# Sheet1.net
KiCad netlist of a schematic drawn in Altium Designer
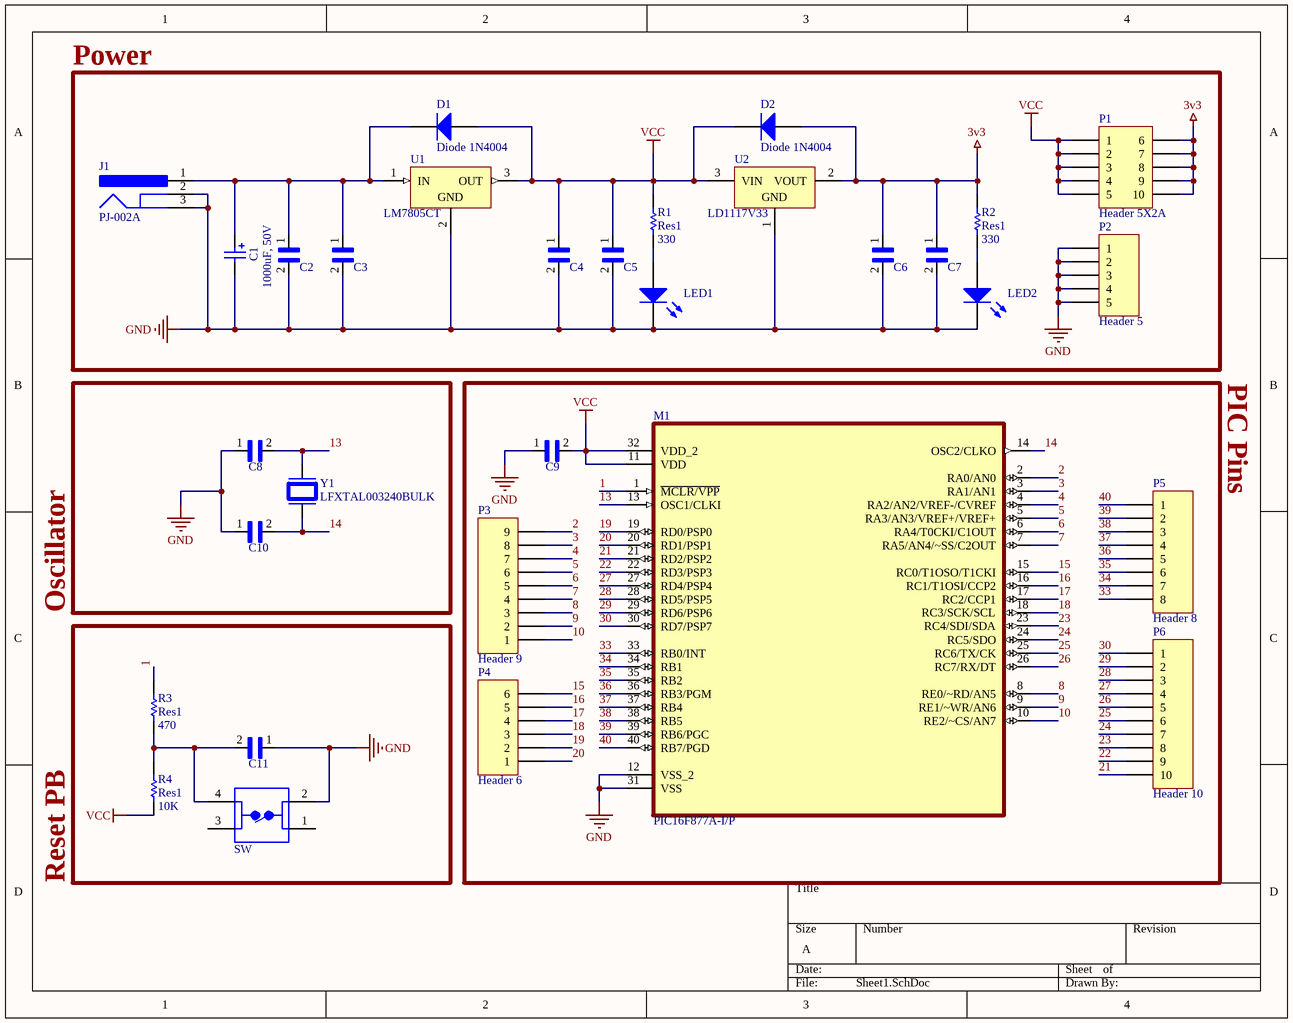
[diagram p0: Sheet1.SchDoc]

(export (version "E")
  (design (tool "Eeschema 10.0.6"))
  (components
    (comp (ref "C1")
      (value "1000uF, 50V")
      (footprint "WCAP-ATG8_D13H25")
      (description "WCAP-ATG8 Aluminum Electrolytic Capacitor, Radial, THT, D13xH25, 1000uF, 50V")
      (fields
        (field (name "MANUFACTURER PART NUMBER") "860010678024")
        (field (name "MANUFACTURER") "Wurth Elektronik")
      )
      (libsource (lib "Aluminium Electrolyt Capacitors") (part "860010678024"))
    )
    (comp (ref "C2")
      (value "RDE5C2A220J0M1H03A")
      (footprint "CAP_RDE5C2A220J0M1H03A")
      (description "Lead Capacitor C0G_EIA_ with Capacitance: 22pF and Rated Voltage: 100Vdc")
      (fields (field (name "MF") "Murata"))
      (libsource (lib "Schlib1") (part "RDE5C2A220J0M1H03A"))
    )
    (comp (ref "C3")
      (value "RDE5C2A220J0M1H03A")
      (footprint "CAP_RDE5C2A220J0M1H03A")
      (description "Lead Capacitor C0G_EIA_ with Capacitance: 22pF and Rated Voltage: 100Vdc")
      (fields (field (name "MF") "Murata"))
      (libsource (lib "Schlib1") (part "RDE5C2A220J0M1H03A"))
    )
    (comp (ref "C4")
      (value "RDE5C2A220J0M1H03A")
      (footprint "CAP_RDE5C2A220J0M1H03A")
      (description "Lead Capacitor C0G_EIA_ with Capacitance: 22pF and Rated Voltage: 100Vdc")
      (fields (field (name "MF") "Murata"))
      (libsource (lib "Schlib1") (part "RDE5C2A220J0M1H03A"))
    )
    (comp (ref "C5")
      (value "RDE5C2A220J0M1H03A")
      (footprint "CAP_RDE5C2A220J0M1H03A")
      (description "Lead Capacitor C0G_EIA_ with Capacitance: 22pF and Rated Voltage: 100Vdc")
      (fields (field (name "MF") "Murata"))
      (libsource (lib "Schlib1") (part "RDE5C2A220J0M1H03A"))
    )
    (comp (ref "C6")
      (value "RDE5C2A220J0M1H03A")
      (footprint "CAP_RDE5C2A220J0M1H03A")
      (description "Lead Capacitor C0G_EIA_ with Capacitance: 22pF and Rated Voltage: 100Vdc")
      (fields (field (name "MF") "Murata"))
      (libsource (lib "Schlib1") (part "RDE5C2A220J0M1H03A"))
    )
    (comp (ref "C7")
      (value "RDE5C2A220J0M1H03A")
      (footprint "CAP_RDE5C2A220J0M1H03A")
      (description "Lead Capacitor C0G_EIA_ with Capacitance: 22pF and Rated Voltage: 100Vdc")
      (fields (field (name "MF") "Murata"))
      (libsource (lib "Schlib1") (part "RDE5C2A220J0M1H03A"))
    )
    (comp (ref "C8")
      (value "RDE5C2A220J0M1H03A")
      (footprint "CAP_RDE5C2A220J0M1H03A")
      (description "Lead Capacitor C0G_EIA_ with Capacitance: 22pF and Rated Voltage: 100Vdc")
      (fields (field (name "MF") "Murata"))
      (libsource (lib "") (part "RDE5C2A220J0M1H03A_2"))
    )
    (comp (ref "C9")
      (value "RDE5C2A220J0M1H03A")
      (footprint "CAP_RDE5C2A220J0M1H03A")
      (description "Lead Capacitor C0G_EIA_ with Capacitance: 22pF and Rated Voltage: 100Vdc")
      (fields (field (name "MF") "Murata"))
      (libsource (lib "") (part "RDE5C2A220J0M1H03A_2"))
    )
    (comp (ref "C10")
      (value "RDE5C2A220J0M1H03A")
      (footprint "CAP_RDE5C2A220J0M1H03A")
      (description "Lead Capacitor C0G_EIA_ with Capacitance: 22pF and Rated Voltage: 100Vdc")
      (fields (field (name "MF") "Murata"))
      (libsource (lib "") (part "RDE5C2A220J0M1H03A_2"))
    )
    (comp (ref "C11")
      (value "RDE5C2A220J0M1H03A")
      (footprint "CAP_RDE5C2A220J0M1H03A")
      (description "Lead Capacitor C0G_EIA_ with Capacitance: 22pF and Rated Voltage: 100Vdc")
      (fields (field (name "MF") "Murata"))
      (libsource (lib "") (part "RDE5C2A220J0M1H03A_1"))
    )
    (comp (ref "D1")
      (value "Diode 1N4004")
      (footprint "DO-41")
      (description "1 Amp General Purpose Rectifier")
      (fields (field (name "PUBLISHER") "Altium Limited"))
      (libsource (lib "Miscellaneous Devices") (part "Diode 1N4004"))
    )
    (comp (ref "D2")
      (value "Diode 1N4004")
      (footprint "DO-41")
      (description "1 Amp General Purpose Rectifier")
      (fields (field (name "PUBLISHER") "Altium Limited"))
      (libsource (lib "Miscellaneous Devices") (part "Diode 1N4004"))
    )
    (comp (ref "J1")
      (value "PJ-002A")
      (footprint "CUI-PJ-002A_V")
      (fields (field (name "MANUFACTURER") "CUIInc."))
      (libsource (lib "Altium Content Vault") (part "JACK-2CD3-RN"))
    )
    (comp (ref "LED1")
      (value "151031SS06000")
      (footprint "Type 3mm")
      (description "THT LED round mono-color color lens, WL-TMRW, Super Red")
      (fields (field (name "MANUFACTURER") "Wuerth Elektronik"))
      (libsource (lib "Altium Content Vault") (part "WE-LED_K1A2-2"))
    )
    (comp (ref "LED2")
      (value "151031SS06000")
      (footprint "Type 3mm")
      (description "THT LED round mono-color color lens, WL-TMRW, Super Red")
      (fields (field (name "MANUFACTURER") "Wuerth Elektronik"))
      (libsource (lib "Altium Content Vault") (part "WE-LED_K1A2-2"))
    )
    (comp (ref "M1")
      (value "PIC16F877A-I/P")
      (footprint "DIP254P1524X483-40")
      (description "PIC PICÂ® 16F Microcontroller IC 8-Bit 20MHz 14KB _8K x 14_ FLASH 40-PDIP")
      (fields (field (name "MF") "Microchip"))
      (libsource (lib "PIC - 16F877A") (part "PIC16F877A-I/P"))
    )
    (comp (ref "P1")
      (value "Header 5X2A")
      (footprint "HDR2X5_CEN")
      (description "Header, 5-Pin, Dual row")
      (fields (field (name "PUBLISHER") "Altium Limited"))
      (libsource (lib "Miscellaneous Connectors") (part "Header 5X2A"))
    )
    (comp (ref "P2")
      (value "Header 5")
      (footprint "HDR1X5")
      (description "Header, 5-Pin")
      (fields (field (name "PUBLISHER") "Altium Limited"))
      (libsource (lib "Miscellaneous Connectors") (part "Header 5"))
    )
    (comp (ref "P3")
      (value "Header 9")
      (footprint "HDR1X9")
      (description "Header, 9-Pin")
      (fields (field (name "PUBLISHER") "Altium Limited"))
      (libsource (lib "Miscellaneous Connectors") (part "Header 9"))
    )
    (comp (ref "P4")
      (value "Header 6")
      (footprint "HDR1X6")
      (description "Header, 6-Pin")
      (fields (field (name "PUBLISHER") "Altium Limited"))
      (libsource (lib "Miscellaneous Connectors") (part "Header 6"))
    )
    (comp (ref "P5")
      (value "Header 8")
      (footprint "HDR1X8")
      (description "Header, 8-Pin")
      (fields (field (name "PUBLISHER") "Altium Limited"))
      (libsource (lib "Miscellaneous Connectors") (part "Header 8"))
    )
    (comp (ref "P6")
      (value "Header 10")
      (footprint "HDR1X10")
      (description "Header, 10-Pin")
      (fields (field (name "PUBLISHER") "Altium Limited"))
      (libsource (lib "Miscellaneous Connectors") (part "Header 10"))
    )
    (comp (ref "R1")
      (value "Res1")
      (footprint "AXIAL-0.3")
      (description "Resistor")
      (fields (field (name "ALTIUM_VALUE") "330") (field (name "PUBLISHER") "Altium Limited"))
      (libsource (lib "Miscellaneous Devices") (part "Res1"))
    )
    (comp (ref "R2")
      (value "Res1")
      (footprint "AXIAL-0.3")
      (description "Resistor")
      (fields (field (name "ALTIUM_VALUE") "330") (field (name "PUBLISHER") "Altium Limited"))
      (libsource (lib "Miscellaneous Devices") (part "Res1"))
    )
    (comp (ref "R3")
      (value "Res1")
      (footprint "AXIAL-0.3")
      (description "Resistor")
      (fields (field (name "ALTIUM_VALUE") "470") (field (name "PUBLISHER") "Altium Limited"))
      (libsource (lib "Miscellaneous Devices") (part "Res1"))
    )
    (comp (ref "R4")
      (value "Res1")
      (footprint "AXIAL-0.3")
      (description "Resistor")
      (fields (field (name "ALTIUM_VALUE") "10K") (field (name "PUBLISHER") "Altium Limited"))
      (libsource (lib "Miscellaneous Devices") (part "Res1"))
    )
    (comp (ref "SW")
      (value "3-1825910-1")
      (footprint "TE_3-1825910-1")
      (description "Switch Push Button OFF _ON_ SPST Round Button 0.05A 24VDC Momentary Contact PC Pins Thru-Hole")
      (fields (field (name "MF") "TE Connectivity"))
      (libsource (lib "Push Button") (part "3-1825910-1"))
    )
    (comp (ref "U1")
      (value "LM7805CT")
      (footprint "FAIR-TO-220-3")
      (description "Positive Voltage Regulator, 5 V, 1 A, -40 to 125 degC, 3-Pin TO-220, RoHS, Tube")
      (fields (field (name "MANUFACTURER") "FairchildSemiconductor"))
      (libsource (lib "Altium Content Vault") (part "FAIR-LM7805CT-TO220-3"))
    )
    (comp (ref "U2")
      (value "LD1117V33")
      (footprint "TO220")
      (description "Fixed Low Drop Positive Voltage Regulator, 3.3V, 3-Pin TO-220")
      (libsource (lib "Altium Content Vault") (part "PM-REG-LD1117V-SIL3"))
    )
    (comp (ref "Y1")
      (value "LFXTAL003240BULK")
      (footprint "HC49P488W45L1105T470H410")
      (description "16MHz Â±30ppm Crystal 30pF 40 Ohms HC-49/US")
      (fields (field (name "MF") "IQD Frequency Products"))
      (libsource (lib "16MHz ±30ppm Crystal 30pF 40 Ohms HC-49US") (part "LFXTAL003240BULK"))
    )
  )
  (nets
    (net (code "1") (name "/1") (class "Default")
      (node (ref "M1") (pin "1") (pinfunction "~{MCLR/VPP}_1") (pintype "input"))
      (node (ref "R3") (pin "2") (pinfunction "2_2") (pintype "passive"))
    )
    (net (code "2") (name "/2") (class "Default")
      (node (ref "M1") (pin "2") (pinfunction "RA0/AN0_2") (pintype "bidirectional"))
      (node (ref "P3") (pin "9") (pinfunction "9_9") (pintype "passive"))
    )
    (net (code "3") (name "/3") (class "Default")
      (node (ref "M1") (pin "3") (pinfunction "RA1/AN1_3") (pintype "bidirectional"))
      (node (ref "P3") (pin "8") (pinfunction "8_8") (pintype "passive"))
    )
    (net (code "4") (name "/4") (class "Default")
      (node (ref "M1") (pin "4") (pinfunction "RA2/AN2/VREF-/CVREF_4") (pintype "bidirectional"))
      (node (ref "P3") (pin "7") (pinfunction "7_7") (pintype "passive"))
    )
    (net (code "5") (name "/5") (class "Default")
      (node (ref "M1") (pin "5") (pinfunction "RA3/AN3/VREF+/VREF+_5") (pintype "bidirectional"))
      (node (ref "P3") (pin "6") (pinfunction "6_6") (pintype "passive"))
    )
    (net (code "6") (name "/6") (class "Default")
      (node (ref "M1") (pin "6") (pinfunction "RA4/T0CKI/C1OUT_6") (pintype "bidirectional"))
      (node (ref "P3") (pin "5") (pinfunction "5_5") (pintype "passive"))
    )
    (net (code "7") (name "/7") (class "Default")
      (node (ref "M1") (pin "7") (pinfunction "RA5/AN4/~SS/C2OUT_7") (pintype "bidirectional"))
      (node (ref "P3") (pin "4") (pinfunction "4_4") (pintype "passive"))
    )
    (net (code "8") (name "/8") (class "Default")
      (node (ref "M1") (pin "8") (pinfunction "RE0/~RD/AN5_8") (pintype "bidirectional"))
      (node (ref "P3") (pin "3") (pinfunction "3_3") (pintype "passive"))
    )
    (net (code "9") (name "/9") (class "Default")
      (node (ref "M1") (pin "9") (pinfunction "RE1/~WR/AN6_9") (pintype "bidirectional"))
      (node (ref "P3") (pin "2") (pinfunction "2_2") (pintype "passive"))
    )
    (net (code "10") (name "/10") (class "Default")
      (node (ref "M1") (pin "10") (pinfunction "RE2/~CS/AN7_10") (pintype "bidirectional"))
      (node (ref "P3") (pin "1") (pinfunction "1_1") (pintype "passive"))
    )
    (net (code "11") (name "/13") (class "Default")
      (node (ref "C8") (pin "2") (pinfunction "2_2") (pintype "passive"))
      (node (ref "M1") (pin "13") (pinfunction "OSC1/CLKI_13") (pintype "input"))
      (node (ref "Y1") (pin "2") (pinfunction "2_2") (pintype "passive"))
    )
    (net (code "12") (name "/14") (class "Default")
      (node (ref "C10") (pin "2") (pinfunction "2_2") (pintype "passive"))
      (node (ref "M1") (pin "14") (pinfunction "OSC2/CLKO_14") (pintype "output"))
      (node (ref "Y1") (pin "1") (pinfunction "1_1") (pintype "passive"))
    )
    (net (code "13") (name "/15") (class "Default")
      (node (ref "M1") (pin "15") (pinfunction "RC0/T1OSO/T1CKI_15") (pintype "bidirectional"))
      (node (ref "P4") (pin "6") (pinfunction "6_6") (pintype "passive"))
    )
    (net (code "14") (name "/16") (class "Default")
      (node (ref "M1") (pin "16") (pinfunction "RC1/T1OSI/CCP2_16") (pintype "bidirectional"))
      (node (ref "P4") (pin "5") (pinfunction "5_5") (pintype "passive"))
    )
    (net (code "15") (name "/17") (class "Default")
      (node (ref "M1") (pin "17") (pinfunction "RC2/CCP1_17") (pintype "bidirectional"))
      (node (ref "P4") (pin "4") (pinfunction "4_4") (pintype "passive"))
    )
    (net (code "16") (name "/18") (class "Default")
      (node (ref "M1") (pin "18") (pinfunction "RC3/SCK/SCL_18") (pintype "bidirectional"))
      (node (ref "P4") (pin "3") (pinfunction "3_3") (pintype "passive"))
    )
    (net (code "17") (name "/19") (class "Default")
      (node (ref "M1") (pin "19") (pinfunction "RD0/PSP0_19") (pintype "bidirectional"))
      (node (ref "P4") (pin "2") (pinfunction "2_2") (pintype "passive"))
    )
    (net (code "18") (name "/20") (class "Default")
      (node (ref "M1") (pin "20") (pinfunction "RD1/PSP1_20") (pintype "bidirectional"))
      (node (ref "P4") (pin "1") (pinfunction "1_1") (pintype "passive"))
    )
    (net (code "19") (name "/21") (class "Default")
      (node (ref "M1") (pin "21") (pinfunction "RD2/PSP2_21") (pintype "bidirectional"))
      (node (ref "P6") (pin "10") (pinfunction "10_10") (pintype "passive"))
    )
    (net (code "20") (name "/22") (class "Default")
      (node (ref "M1") (pin "22") (pinfunction "RD3/PSP3_22") (pintype "bidirectional"))
      (node (ref "P6") (pin "9") (pinfunction "9_9") (pintype "passive"))
    )
    (net (code "21") (name "/23") (class "Default")
      (node (ref "M1") (pin "23") (pinfunction "RC4/SDI/SDA_23") (pintype "bidirectional"))
      (node (ref "P6") (pin "8") (pinfunction "8_8") (pintype "passive"))
    )
    (net (code "22") (name "/24") (class "Default")
      (node (ref "M1") (pin "24") (pinfunction "RC5/SDO_24") (pintype "bidirectional"))
      (node (ref "P6") (pin "7") (pinfunction "7_7") (pintype "passive"))
    )
    (net (code "23") (name "/25") (class "Default")
      (node (ref "M1") (pin "25") (pinfunction "RC6/TX/CK_25") (pintype "bidirectional"))
      (node (ref "P6") (pin "6") (pinfunction "6_6") (pintype "passive"))
    )
    (net (code "24") (name "/26") (class "Default")
      (node (ref "M1") (pin "26") (pinfunction "RC7/RX/DT_26") (pintype "bidirectional"))
      (node (ref "P6") (pin "5") (pinfunction "5_5") (pintype "passive"))
    )
    (net (code "25") (name "/27") (class "Default")
      (node (ref "M1") (pin "27") (pinfunction "RD4/PSP4_27") (pintype "bidirectional"))
      (node (ref "P6") (pin "4") (pinfunction "4_4") (pintype "passive"))
    )
    (net (code "26") (name "/28") (class "Default")
      (node (ref "M1") (pin "28") (pinfunction "RD5/PSP5_28") (pintype "bidirectional"))
      (node (ref "P6") (pin "3") (pinfunction "3_3") (pintype "passive"))
    )
    (net (code "27") (name "/29") (class "Default")
      (node (ref "M1") (pin "29") (pinfunction "RD6/PSP6_29") (pintype "bidirectional"))
      (node (ref "P6") (pin "2") (pinfunction "2_2") (pintype "passive"))
    )
    (net (code "28") (name "/30") (class "Default")
      (node (ref "M1") (pin "30") (pinfunction "RD7/PSP7_30") (pintype "bidirectional"))
      (node (ref "P6") (pin "1") (pinfunction "1_1") (pintype "passive"))
    )
    (net (code "29") (name "/33") (class "Default")
      (node (ref "M1") (pin "33") (pinfunction "RB0/INT_33") (pintype "bidirectional"))
      (node (ref "P5") (pin "8") (pinfunction "8_8") (pintype "passive"))
    )
    (net (code "30") (name "/34") (class "Default")
      (node (ref "M1") (pin "34") (pinfunction "RB1_34") (pintype "bidirectional"))
      (node (ref "P5") (pin "7") (pinfunction "7_7") (pintype "passive"))
    )
    (net (code "31") (name "/35") (class "Default")
      (node (ref "M1") (pin "35") (pinfunction "RB2_35") (pintype "bidirectional"))
      (node (ref "P5") (pin "6") (pinfunction "6_6") (pintype "passive"))
    )
    (net (code "32") (name "/36") (class "Default")
      (node (ref "M1") (pin "36") (pinfunction "RB3/PGM_36") (pintype "bidirectional"))
      (node (ref "P5") (pin "5") (pinfunction "5_5") (pintype "passive"))
    )
    (net (code "33") (name "/37") (class "Default")
      (node (ref "M1") (pin "37") (pinfunction "RB4_37") (pintype "bidirectional"))
      (node (ref "P5") (pin "4") (pinfunction "4_4") (pintype "passive"))
    )
    (net (code "34") (name "/38") (class "Default")
      (node (ref "M1") (pin "38") (pinfunction "RB5_38") (pintype "bidirectional"))
      (node (ref "P5") (pin "3") (pinfunction "3_3") (pintype "passive"))
    )
    (net (code "35") (name "/39") (class "Default")
      (node (ref "M1") (pin "39") (pinfunction "RB6/PGC_39") (pintype "bidirectional"))
      (node (ref "P5") (pin "2") (pinfunction "2_2") (pintype "passive"))
    )
    (net (code "36") (name "/40") (class "Default")
      (node (ref "M1") (pin "40") (pinfunction "RB7/PGD_40") (pintype "bidirectional"))
      (node (ref "P5") (pin "1") (pinfunction "1_1") (pintype "passive"))
    )
    (net (code "37") (name "3v3") (class "Default")
      (node (ref "C6") (pin "1") (pinfunction "1_1") (pintype "passive"))
      (node (ref "C7") (pin "1") (pinfunction "1_1") (pintype "passive"))
      (node (ref "D2") (pin "1") (pinfunction "A_1") (pintype "passive"))
      (node (ref "P1") (pin "10") (pinfunction "10_10") (pintype "passive"))
      (node (ref "P1") (pin "6") (pinfunction "6_6") (pintype "passive"))
      (node (ref "P1") (pin "7") (pinfunction "7_7") (pintype "passive"))
      (node (ref "P1") (pin "8") (pinfunction "8_8") (pintype "passive"))
      (node (ref "P1") (pin "9") (pinfunction "9_9") (pintype "passive"))
      (node (ref "R2") (pin "1") (pinfunction "1_1") (pintype "passive"))
      (node (ref "U2") (pin "2") (pinfunction "VOUT_2") (pintype "power_in"))
    )
    (net (code "38") (name "GND") (class "Default")
      (node (ref "C1") (pin "2") (pinfunction "N_2") (pintype "passive"))
      (node (ref "C10") (pin "1") (pinfunction "1_1") (pintype "passive"))
      (node (ref "C11") (pin "1") (pinfunction "1_1") (pintype "passive"))
      (node (ref "C2") (pin "2") (pinfunction "2_2") (pintype "passive"))
      (node (ref "C3") (pin "2") (pinfunction "2_2") (pintype "passive"))
      (node (ref "C4") (pin "2") (pinfunction "2_2") (pintype "passive"))
      (node (ref "C5") (pin "2") (pinfunction "2_2") (pintype "passive"))
      (node (ref "C6") (pin "2") (pinfunction "2_2") (pintype "passive"))
      (node (ref "C7") (pin "2") (pinfunction "2_2") (pintype "passive"))
      (node (ref "C8") (pin "1") (pinfunction "1_1") (pintype "passive"))
      (node (ref "C9") (pin "1") (pinfunction "1_1") (pintype "passive"))
      (node (ref "J1") (pin "2") (pinfunction "2_2") (pintype "passive"))
      (node (ref "J1") (pin "3") (pinfunction "3_3") (pintype "passive"))
      (node (ref "LED1") (pin "1") (pinfunction "K_1") (pintype "passive"))
      (node (ref "LED2") (pin "1") (pinfunction "K_1") (pintype "passive"))
      (node (ref "M1") (pin "12") (pinfunction "VSS_2_12") (pintype "power_in"))
      (node (ref "M1") (pin "31") (pinfunction "VSS_31") (pintype "power_in"))
      (node (ref "P2") (pin "1") (pinfunction "1_1") (pintype "passive"))
      (node (ref "P2") (pin "2") (pinfunction "2_2") (pintype "passive"))
      (node (ref "P2") (pin "3") (pinfunction "3_3") (pintype "passive"))
      (node (ref "P2") (pin "4") (pinfunction "4_4") (pintype "passive"))
      (node (ref "P2") (pin "5") (pinfunction "5_5") (pintype "passive"))
      (node (ref "SW") (pin "2") (pinfunction "2_2") (pintype "passive"))
      (node (ref "U1") (pin "2") (pinfunction "GND_2") (pintype "power_in"))
      (node (ref "U2") (pin "1") (pinfunction "GND_1") (pintype "power_in"))
    )
    (net (code "39") (name "Net-(C1-P)") (class "Default")
      (node (ref "C1") (pin "1") (pinfunction "P_1") (pintype "passive"))
      (node (ref "C2") (pin "1") (pinfunction "1_1") (pintype "passive"))
      (node (ref "C3") (pin "1") (pinfunction "1_1") (pintype "passive"))
      (node (ref "D1") (pin "2") (pinfunction "K_2") (pintype "passive"))
      (node (ref "J1") (pin "1") (pinfunction "1_1") (pintype "passive"))
      (node (ref "U1") (pin "1") (pinfunction "IN_1") (pintype "input"))
    )
    (net (code "40") (name "Net-(C11-Pad2)") (class "Default")
      (node (ref "C11") (pin "2") (pinfunction "2_2") (pintype "passive"))
      (node (ref "R3") (pin "1") (pinfunction "1_1") (pintype "passive"))
      (node (ref "R4") (pin "2") (pinfunction "2_2") (pintype "passive"))
      (node (ref "SW") (pin "4") (pinfunction "4_4") (pintype "passive"))
    )
    (net (code "41") (name "Net-(LED1-A)") (class "Default")
      (node (ref "LED1") (pin "2") (pinfunction "A_2") (pintype "passive"))
      (node (ref "R1") (pin "2") (pinfunction "2_2") (pintype "passive"))
    )
    (net (code "42") (name "Net-(LED2-A)") (class "Default")
      (node (ref "LED2") (pin "2") (pinfunction "A_2") (pintype "passive"))
      (node (ref "R2") (pin "2") (pinfunction "2_2") (pintype "passive"))
    )
    (net (code "43") (name "VCC") (class "Default")
      (node (ref "C4") (pin "1") (pinfunction "1_1") (pintype "passive"))
      (node (ref "C5") (pin "1") (pinfunction "1_1") (pintype "passive"))
      (node (ref "C9") (pin "2") (pinfunction "2_2") (pintype "passive"))
      (node (ref "D1") (pin "1") (pinfunction "A_1") (pintype "passive"))
      (node (ref "D2") (pin "2") (pinfunction "K_2") (pintype "passive"))
      (node (ref "M1") (pin "11") (pinfunction "VDD_11") (pintype "power_in"))
      (node (ref "M1") (pin "32") (pinfunction "VDD_2_32") (pintype "power_in"))
      (node (ref "P1") (pin "1") (pinfunction "1_1") (pintype "passive"))
      (node (ref "P1") (pin "2") (pinfunction "2_2") (pintype "passive"))
      (node (ref "P1") (pin "3") (pinfunction "3_3") (pintype "passive"))
      (node (ref "P1") (pin "4") (pinfunction "4_4") (pintype "passive"))
      (node (ref "P1") (pin "5") (pinfunction "5_5") (pintype "passive"))
      (node (ref "R1") (pin "1") (pinfunction "1_1") (pintype "passive"))
      (node (ref "R4") (pin "1") (pinfunction "1_1") (pintype "passive"))
      (node (ref "U1") (pin "3") (pinfunction "OUT_3") (pintype "output"))
      (node (ref "U2") (pin "3") (pinfunction "VIN_3") (pintype "power_in"))
    )
    (net (code "44") (name "unconnected-(SW-Pad1)") (class "Default")
      (node (ref "SW") (pin "1") (pinfunction "1_1") (pintype "passive"))
    )
    (net (code "45") (name "unconnected-(SW-Pad3)") (class "Default")
      (node (ref "SW") (pin "3") (pinfunction "3_3") (pintype "passive"))
    )
  )
)
